# fuente.net
KiCad netlist of a schematic drawn in EAGLE
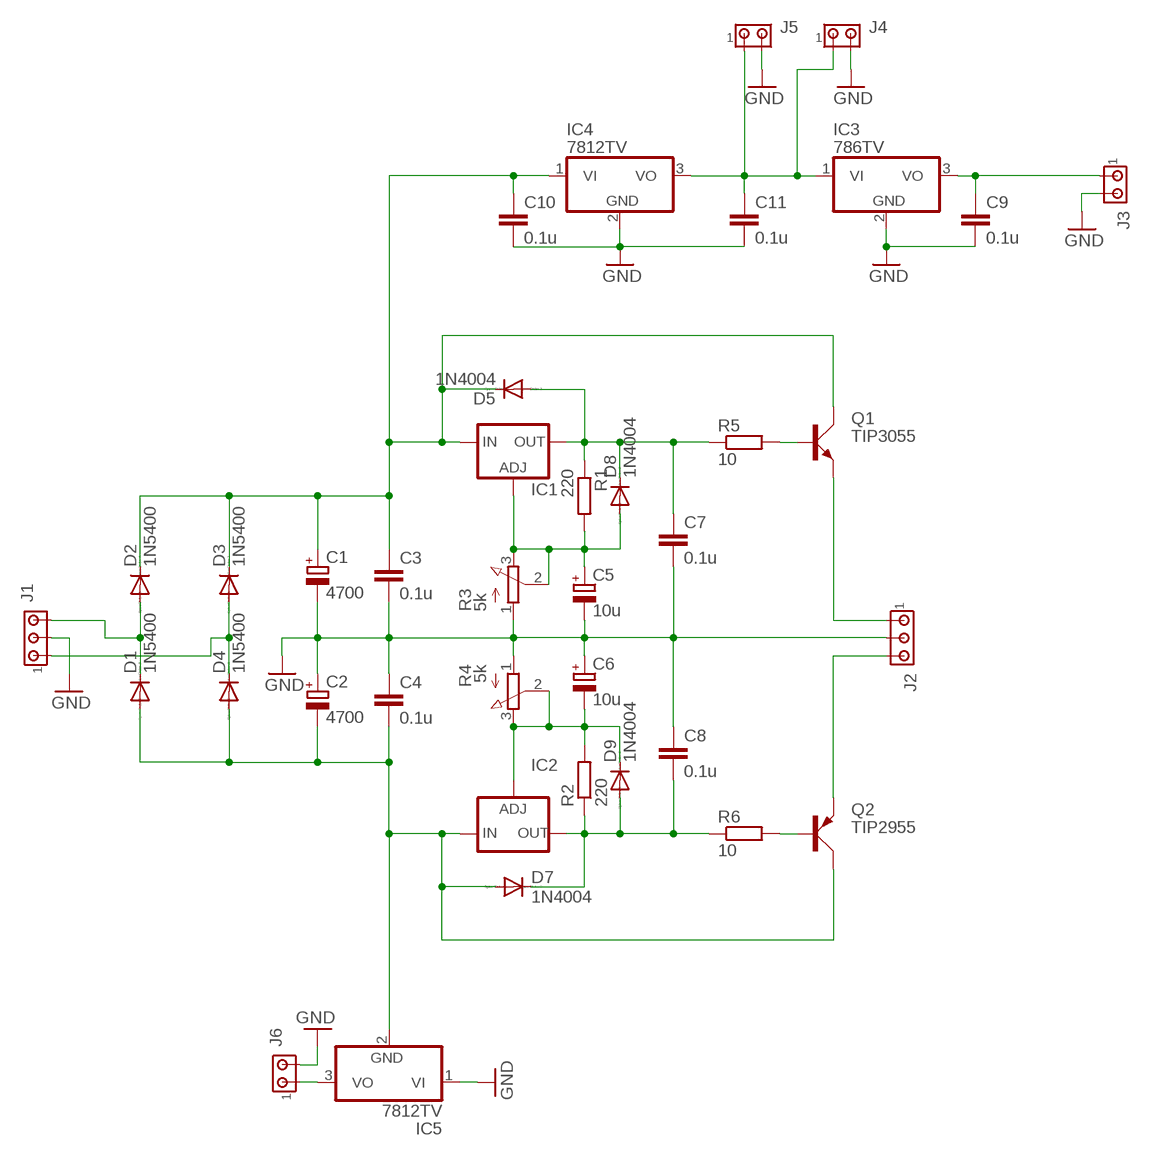
[diagram p0: schematic, sheet 1]

(export (version "E")
  (design (tool "Eeschema 10.0.6"))
  (components
    (comp (ref "C1")
      (value "4700")
      (footprint "eagle-import:EB22,5D")
      (libsource (lib "eagle-import") (part "CPOL-EUE10-22.5"))
    )
    (comp (ref "C2")
      (value "4700")
      (footprint "eagle-import:EB22,5D")
      (libsource (lib "eagle-import") (part "CPOL-EUE10-22.5"))
    )
    (comp (ref "C3")
      (value "0.1u")
      (footprint "eagle-import:C025-024X044")
      (libsource (lib "eagle-import") (part "C-EU025-024X044"))
    )
    (comp (ref "C4")
      (value "0.1u")
      (footprint "eagle-import:C025-024X044")
      (libsource (lib "eagle-import") (part "C-EU025-024X044"))
    )
    (comp (ref "C5")
      (value "10u")
      (footprint "eagle-import:E2,5-5")
      (libsource (lib "eagle-import") (part "CPOL-EUE2.5-5"))
    )
    (comp (ref "C6")
      (value "10u")
      (footprint "eagle-import:E2,5-5")
      (libsource (lib "eagle-import") (part "CPOL-EUE2.5-5"))
    )
    (comp (ref "C7")
      (value "0.1u")
      (footprint "eagle-import:C025-024X044")
      (libsource (lib "eagle-import") (part "C-EU025-024X044"))
    )
    (comp (ref "C8")
      (value "0.1u")
      (footprint "eagle-import:C025-024X044")
      (libsource (lib "eagle-import") (part "C-EU025-024X044"))
    )
    (comp (ref "C9")
      (value "0.1u")
      (footprint "eagle-import:C025-024X044")
      (libsource (lib "eagle-import") (part "C-EU025-024X044"))
    )
    (comp (ref "C10")
      (value "0.1u")
      (footprint "eagle-import:C025-024X044")
      (libsource (lib "eagle-import") (part "C-EU025-024X044"))
    )
    (comp (ref "C11")
      (value "0.1u")
      (footprint "eagle-import:C025-024X044")
      (libsource (lib "eagle-import") (part "C-EU025-024X044"))
    )
    (comp (ref "D1")
      (value "1N5400")
      (footprint "eagle-import:DO201-15")
      (libsource (lib "eagle-import") (part "1N5400"))
    )
    (comp (ref "D2")
      (value "1N5400")
      (footprint "eagle-import:DO201-15")
      (libsource (lib "eagle-import") (part "1N5400"))
    )
    (comp (ref "D3")
      (value "1N5400")
      (footprint "eagle-import:DO201-15")
      (libsource (lib "eagle-import") (part "1N5400"))
    )
    (comp (ref "D4")
      (value "1N5400")
      (footprint "eagle-import:DO201-15")
      (libsource (lib "eagle-import") (part "1N5400"))
    )
    (comp (ref "D5")
      (value "1N4004")
      (footprint "eagle-import:DO41-10")
      (libsource (lib "eagle-import") (part "1N4004"))
    )
    (comp (ref "D7")
      (value "1N4004")
      (footprint "eagle-import:DO41-10")
      (libsource (lib "eagle-import") (part "1N4004"))
    )
    (comp (ref "D8")
      (value "1N4004")
      (footprint "eagle-import:DO41-10")
      (libsource (lib "eagle-import") (part "1N4004"))
    )
    (comp (ref "D9")
      (value "1N4004")
      (footprint "eagle-import:DO41-10")
      (libsource (lib "eagle-import") (part "1N4004"))
    )
    (comp (ref "IC1")
      (value "LM317TS")
      (footprint "eagle-import:317TS")
      (libsource (lib "eagle-import") (part "LM317TS"))
    )
    (comp (ref "IC2")
      (value "LM337TS")
      (footprint "eagle-import:337TS")
      (libsource (lib "eagle-import") (part "LM337TS"))
    )
    (comp (ref "IC3")
      (value "786TV")
      (footprint "eagle-import:TO220V")
      (libsource (lib "eagle-import") (part "78TV6"))
    )
    (comp (ref "IC4")
      (value "7812TV")
      (footprint "eagle-import:TO220V")
      (libsource (lib "eagle-import") (part "78TV12"))
    )
    (comp (ref "IC5")
      (value "7812TV")
      (footprint "eagle-import:TO220V")
      (libsource (lib "eagle-import") (part "78TV12"))
    )
    (comp (ref "J1")
      (value "MTA03-156")
      (footprint "eagle-import:1X3MTA")
      (libsource (lib "eagle-import") (part "MTA03-156"))
    )
    (comp (ref "J2")
      (value "MTA03-156")
      (footprint "eagle-import:1X3MTA")
      (libsource (lib "eagle-import") (part "MTA03-156"))
    )
    (comp (ref "J3")
      (value "MTA02-100")
      (footprint "eagle-import:10X02MTA")
      (libsource (lib "eagle-import") (part "MTA02-100"))
    )
    (comp (ref "J4")
      (value "MTA02-100")
      (footprint "eagle-import:10X02MTA")
      (libsource (lib "eagle-import") (part "MTA02-100"))
    )
    (comp (ref "J5")
      (value "MTA02-100")
      (footprint "eagle-import:10X02MTA")
      (libsource (lib "eagle-import") (part "MTA02-100"))
    )
    (comp (ref "J6")
      (value "MTA02-100")
      (footprint "eagle-import:10X02MTA")
      (libsource (lib "eagle-import") (part "MTA02-100"))
    )
    (comp (ref "Q1")
      (value "TIP3055")
      (footprint "eagle-import:TOP3AV")
      (libsource (lib "eagle-import") (part "TIP3055"))
    )
    (comp (ref "Q2")
      (value "TIP2955")
      (footprint "eagle-import:TOP3AV")
      (libsource (lib "eagle-import") (part "TIP2955"))
    )
    (comp (ref "R1")
      (value "220")
      (footprint "eagle-import:0204_7")
      (libsource (lib "eagle-import") (part "R-EU_0204/7"))
    )
    (comp (ref "R2")
      (value "220")
      (footprint "eagle-import:0204_7")
      (libsource (lib "eagle-import") (part "R-EU_0204/7"))
    )
    (comp (ref "R3")
      (value "5k")
      (footprint "eagle-import:3RP_1610N")
      (libsource (lib "eagle-import") (part "3RP/1610N"))
    )
    (comp (ref "R4")
      (value "5k")
      (footprint "eagle-import:3RP_1610N")
      (libsource (lib "eagle-import") (part "3RP/1610N"))
    )
    (comp (ref "R5")
      (value "10")
      (footprint "eagle-import:0204_7")
      (libsource (lib "eagle-import") (part "R-EU_0204/7"))
    )
    (comp (ref "R6")
      (value "10")
      (footprint "eagle-import:0204_7")
      (libsource (lib "eagle-import") (part "R-EU_0204/7"))
    )
  )
  (nets
    (net (code "1") (name "GND") (class "Default")
      (node (ref "C1") (pin "-") (pinfunction "-_-") (pintype "passive"))
      (node (ref "C10") (pin "2") (pinfunction "2_2") (pintype "passive"))
      (node (ref "C11") (pin "2") (pinfunction "2_2") (pintype "passive"))
      (node (ref "C2") (pin "+") (pinfunction "+_+") (pintype "passive"))
      (node (ref "C3") (pin "2") (pinfunction "2_2") (pintype "passive"))
      (node (ref "C4") (pin "1") (pinfunction "1_1") (pintype "passive"))
      (node (ref "C5") (pin "-") (pinfunction "-_-") (pintype "passive"))
      (node (ref "C6") (pin "+") (pinfunction "+_+") (pintype "passive"))
      (node (ref "C7") (pin "2") (pinfunction "2_2") (pintype "passive"))
      (node (ref "C8") (pin "1") (pinfunction "1_1") (pintype "passive"))
      (node (ref "C9") (pin "2") (pinfunction "2_2") (pintype "passive"))
      (node (ref "IC3") (pin "2") (pinfunction "GND_2") (pintype "passive"))
      (node (ref "IC4") (pin "2") (pinfunction "GND_2") (pintype "passive"))
      (node (ref "IC5") (pin "1") (pinfunction "VI_1") (pintype "input"))
      (node (ref "J1") (pin "2") (pinfunction "2_2") (pintype "passive"))
      (node (ref "J2") (pin "2") (pinfunction "2_2") (pintype "passive"))
      (node (ref "J3") (pin "2") (pinfunction "2_2") (pintype "passive"))
      (node (ref "J4") (pin "2") (pinfunction "2_2") (pintype "passive"))
      (node (ref "J5") (pin "2") (pinfunction "2_2") (pintype "passive"))
      (node (ref "J6") (pin "2") (pinfunction "2_2") (pintype "passive"))
      (node (ref "R3") (pin "1") (pinfunction "A_1") (pintype "passive"))
      (node (ref "R4") (pin "1") (pinfunction "A_1") (pintype "passive"))
    )
    (net (code "2") (name "Net-(D1-PadC)") (class "Default")
      (node (ref "D1") (pin "C") (pinfunction "C_C") (pintype "passive"))
      (node (ref "D2") (pin "A") (pinfunction "A_A") (pintype "passive"))
      (node (ref "J1") (pin "3") (pinfunction "3_3") (pintype "passive"))
    )
    (net (code "3") (name "Net-(D3-PadA)") (class "Default")
      (node (ref "D3") (pin "A") (pinfunction "A_A") (pintype "passive"))
      (node (ref "D4") (pin "C") (pinfunction "C_C") (pintype "passive"))
      (node (ref "J1") (pin "1") (pinfunction "1_1") (pintype "passive"))
    )
    (net (code "4") (name "Net-(IC1-ADJ)") (class "Default")
      (node (ref "C5") (pin "+") (pinfunction "+_+") (pintype "passive"))
      (node (ref "D8") (pin "A") (pinfunction "A_A") (pintype "passive"))
      (node (ref "IC1") (pin "1") (pinfunction "ADJ_1") (pintype "input"))
      (node (ref "R1") (pin "2") (pinfunction "2_2") (pintype "passive"))
      (node (ref "R3") (pin "2") (pinfunction "S_2") (pintype "passive"))
      (node (ref "R3") (pin "3") (pinfunction "E_3") (pintype "passive"))
    )
    (net (code "5") (name "Net-(IC1-IN)") (class "Default")
      (node (ref "C1") (pin "+") (pinfunction "+_+") (pintype "passive"))
      (node (ref "C10") (pin "1") (pinfunction "1_1") (pintype "passive"))
      (node (ref "C3") (pin "1") (pinfunction "1_1") (pintype "passive"))
      (node (ref "D2") (pin "C") (pinfunction "C_C") (pintype "passive"))
      (node (ref "D3") (pin "C") (pinfunction "C_C") (pintype "passive"))
      (node (ref "D5") (pin "C") (pinfunction "C_C") (pintype "passive"))
      (node (ref "IC1") (pin "3") (pinfunction "IN_3") (pintype "input"))
      (node (ref "IC4") (pin "1") (pinfunction "VI_1") (pintype "input"))
      (node (ref "Q1") (pin "C") (pinfunction "C_C") (pintype "passive"))
    )
    (net (code "6") (name "Net-(IC1-OUT)") (class "Default")
      (node (ref "C7") (pin "1") (pinfunction "1_1") (pintype "passive"))
      (node (ref "D5") (pin "A") (pinfunction "A_A") (pintype "passive"))
      (node (ref "D8") (pin "C") (pinfunction "C_C") (pintype "passive"))
      (node (ref "IC1") (pin "2") (pinfunction "OUT_2") (pintype "passive"))
      (node (ref "R1") (pin "1") (pinfunction "1_1") (pintype "passive"))
      (node (ref "R5") (pin "1") (pinfunction "1_1") (pintype "passive"))
    )
    (net (code "7") (name "Net-(IC2-ADJ)") (class "Default")
      (node (ref "C6") (pin "-") (pinfunction "-_-") (pintype "passive"))
      (node (ref "D9") (pin "C") (pinfunction "C_C") (pintype "passive"))
      (node (ref "IC2") (pin "1") (pinfunction "ADJ_1") (pintype "input"))
      (node (ref "R2") (pin "2") (pinfunction "2_2") (pintype "passive"))
      (node (ref "R4") (pin "2") (pinfunction "S_2") (pintype "passive"))
      (node (ref "R4") (pin "3") (pinfunction "E_3") (pintype "passive"))
    )
    (net (code "8") (name "Net-(IC2-IN)") (class "Default")
      (node (ref "C2") (pin "-") (pinfunction "-_-") (pintype "passive"))
      (node (ref "C4") (pin "2") (pinfunction "2_2") (pintype "passive"))
      (node (ref "D1") (pin "A") (pinfunction "A_A") (pintype "passive"))
      (node (ref "D4") (pin "A") (pinfunction "A_A") (pintype "passive"))
      (node (ref "D7") (pin "A") (pinfunction "A_A") (pintype "passive"))
      (node (ref "IC2") (pin "2") (pinfunction "IN_2") (pintype "input"))
      (node (ref "IC5") (pin "2") (pinfunction "GND_2") (pintype "passive"))
      (node (ref "Q2") (pin "C") (pinfunction "C_C") (pintype "passive"))
    )
    (net (code "9") (name "Net-(IC2-OUT)") (class "Default")
      (node (ref "C8") (pin "2") (pinfunction "2_2") (pintype "passive"))
      (node (ref "D7") (pin "C") (pinfunction "C_C") (pintype "passive"))
      (node (ref "D9") (pin "A") (pinfunction "A_A") (pintype "passive"))
      (node (ref "IC2") (pin "3") (pinfunction "OUT_3") (pintype "passive"))
      (node (ref "R2") (pin "1") (pinfunction "1_1") (pintype "passive"))
      (node (ref "R6") (pin "1") (pinfunction "1_1") (pintype "passive"))
    )
    (net (code "10") (name "Net-(IC3-VI)") (class "Default")
      (node (ref "C11") (pin "1") (pinfunction "1_1") (pintype "passive"))
      (node (ref "IC3") (pin "1") (pinfunction "VI_1") (pintype "input"))
      (node (ref "IC4") (pin "3") (pinfunction "VO_3") (pintype "passive"))
      (node (ref "J4") (pin "1") (pinfunction "1_1") (pintype "passive"))
      (node (ref "J5") (pin "1") (pinfunction "1_1") (pintype "passive"))
    )
    (net (code "11") (name "Net-(IC3-VO)") (class "Default")
      (node (ref "C9") (pin "1") (pinfunction "1_1") (pintype "passive"))
      (node (ref "IC3") (pin "3") (pinfunction "VO_3") (pintype "passive"))
      (node (ref "J3") (pin "1") (pinfunction "1_1") (pintype "passive"))
    )
    (net (code "12") (name "Net-(IC5-VO)") (class "Default")
      (node (ref "IC5") (pin "3") (pinfunction "VO_3") (pintype "passive"))
      (node (ref "J6") (pin "1") (pinfunction "1_1") (pintype "passive"))
    )
    (net (code "13") (name "Net-(J2-Pad1)") (class "Default")
      (node (ref "J2") (pin "1") (pinfunction "1_1") (pintype "passive"))
      (node (ref "Q1") (pin "E") (pinfunction "E_E") (pintype "passive"))
    )
    (net (code "14") (name "Net-(J2-Pad3)") (class "Default")
      (node (ref "J2") (pin "3") (pinfunction "3_3") (pintype "passive"))
      (node (ref "Q2") (pin "E") (pinfunction "E_E") (pintype "passive"))
    )
    (net (code "15") (name "Net-(Q1-PadB)") (class "Default")
      (node (ref "Q1") (pin "B") (pinfunction "B_B") (pintype "passive"))
      (node (ref "R5") (pin "2") (pinfunction "2_2") (pintype "passive"))
    )
    (net (code "16") (name "Net-(Q2-PadB)") (class "Default")
      (node (ref "Q2") (pin "B") (pinfunction "B_B") (pintype "passive"))
      (node (ref "R6") (pin "2") (pinfunction "2_2") (pintype "passive"))
    )
  )
)
